# LDAQ-MINI.net
KiCad netlist of a schematic drawn in EAGLE
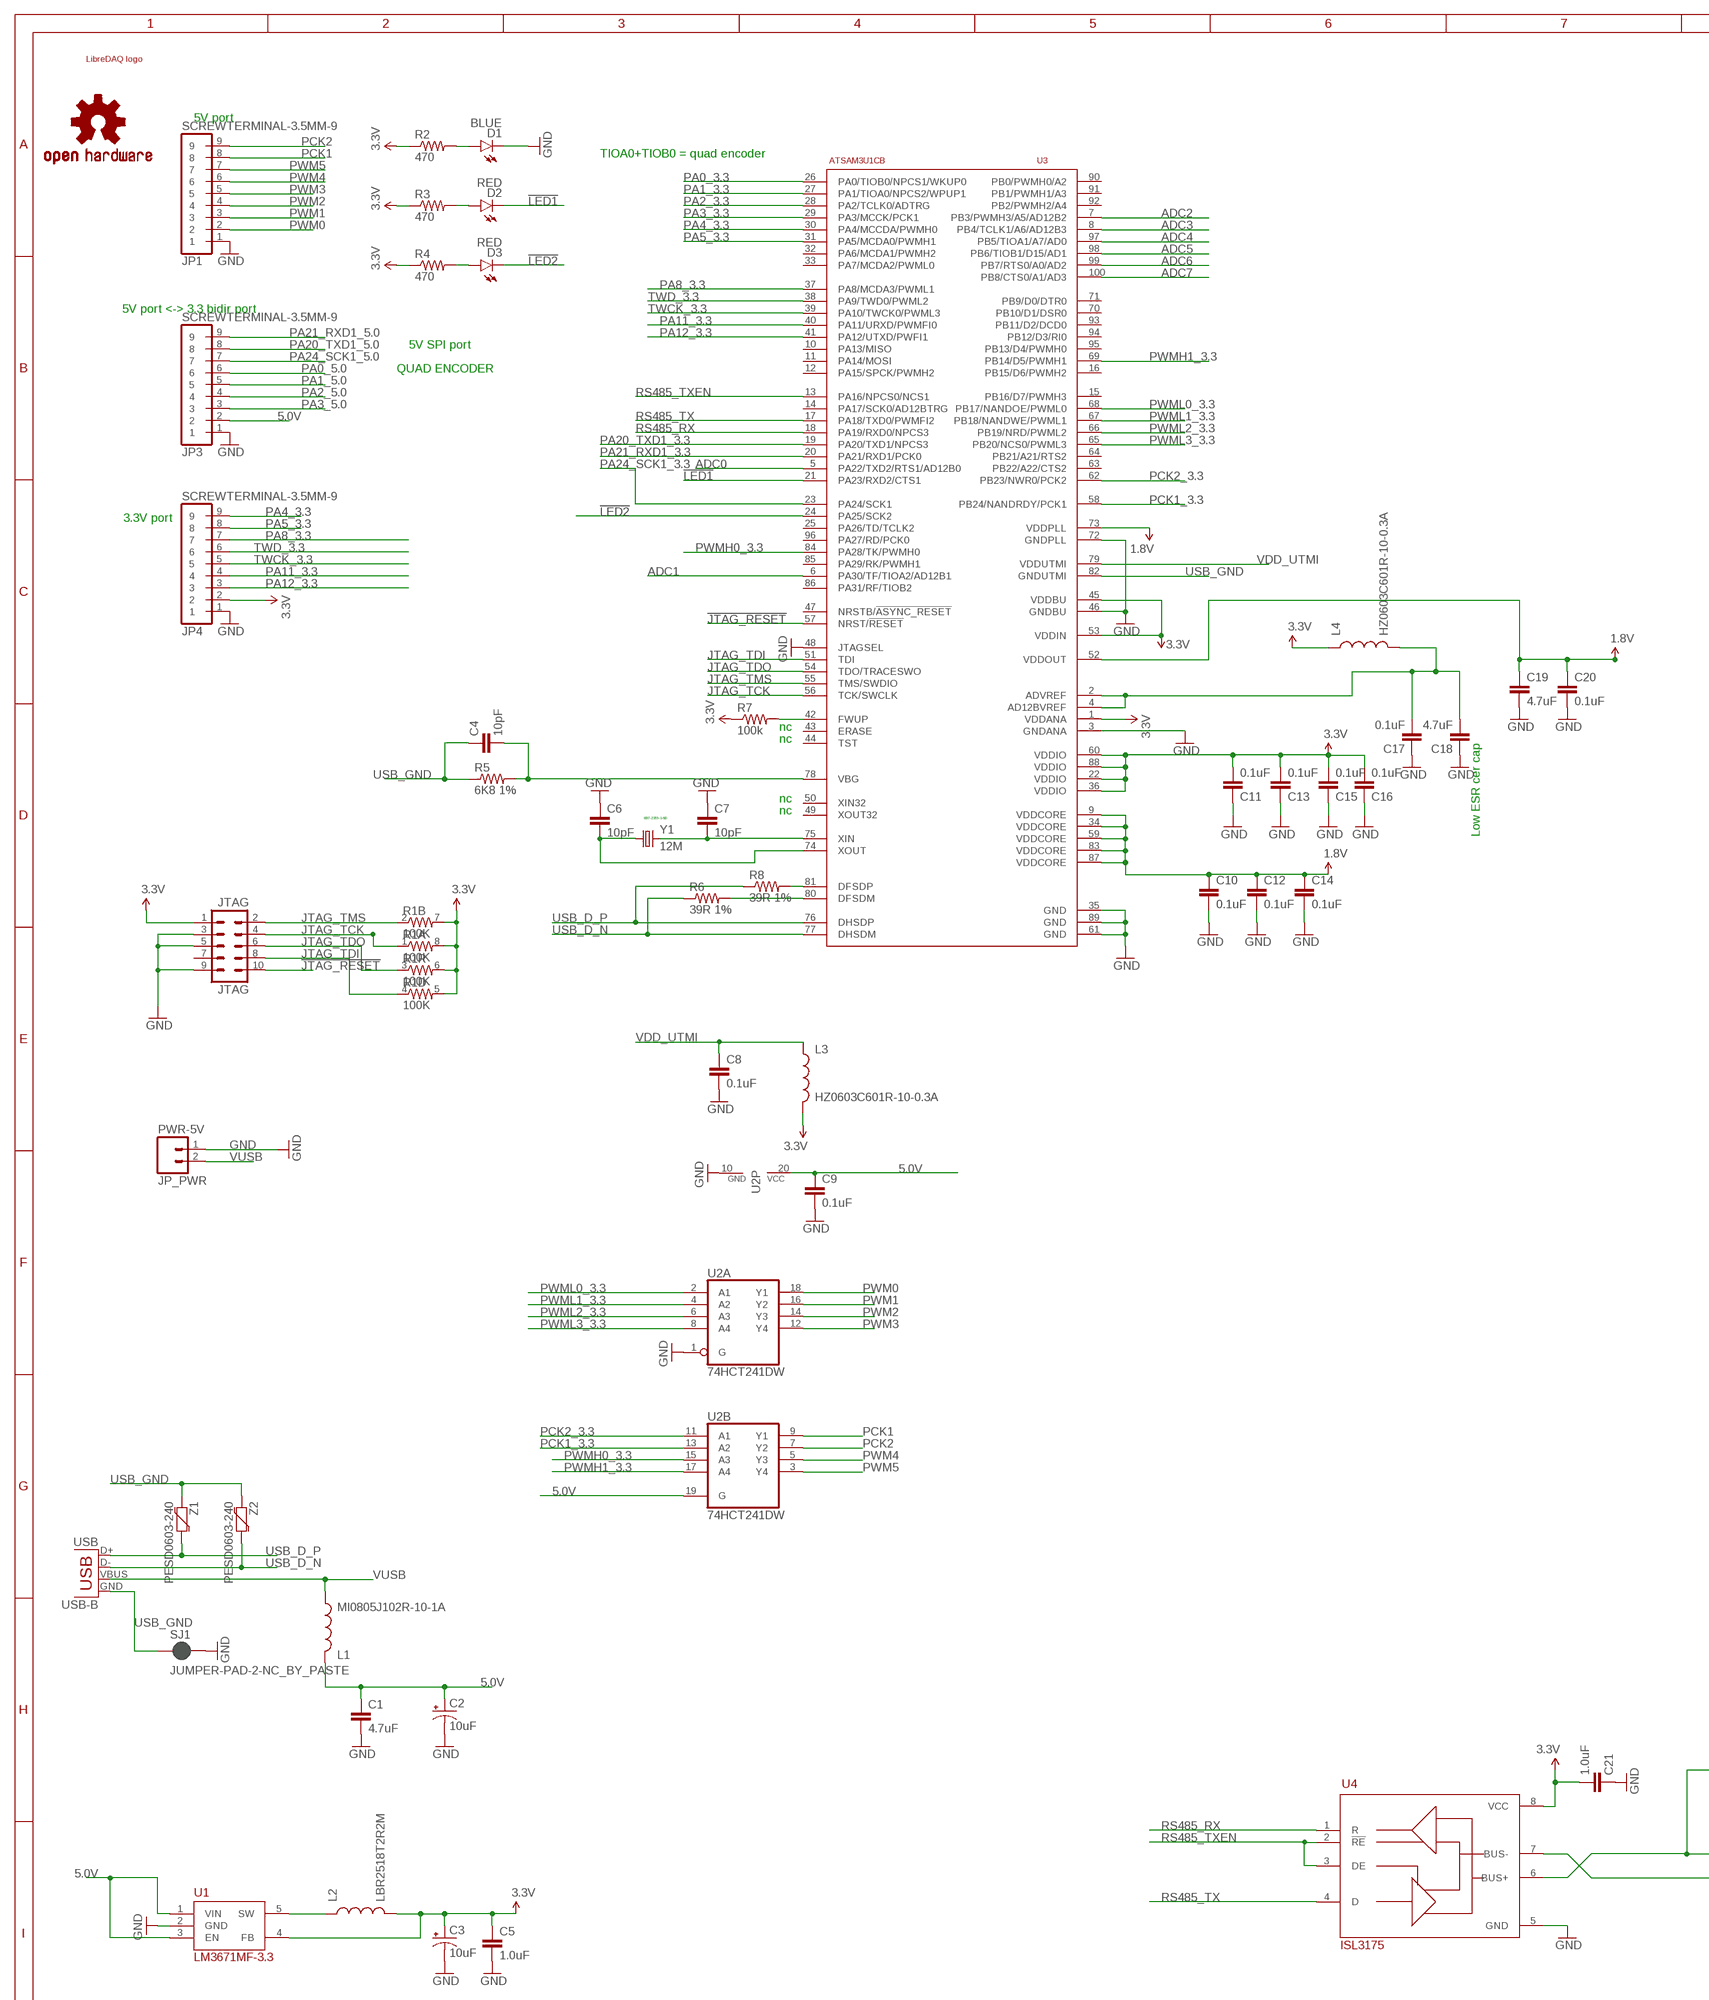
[diagram p0: schematic, sheet 1, part 1 of 2]
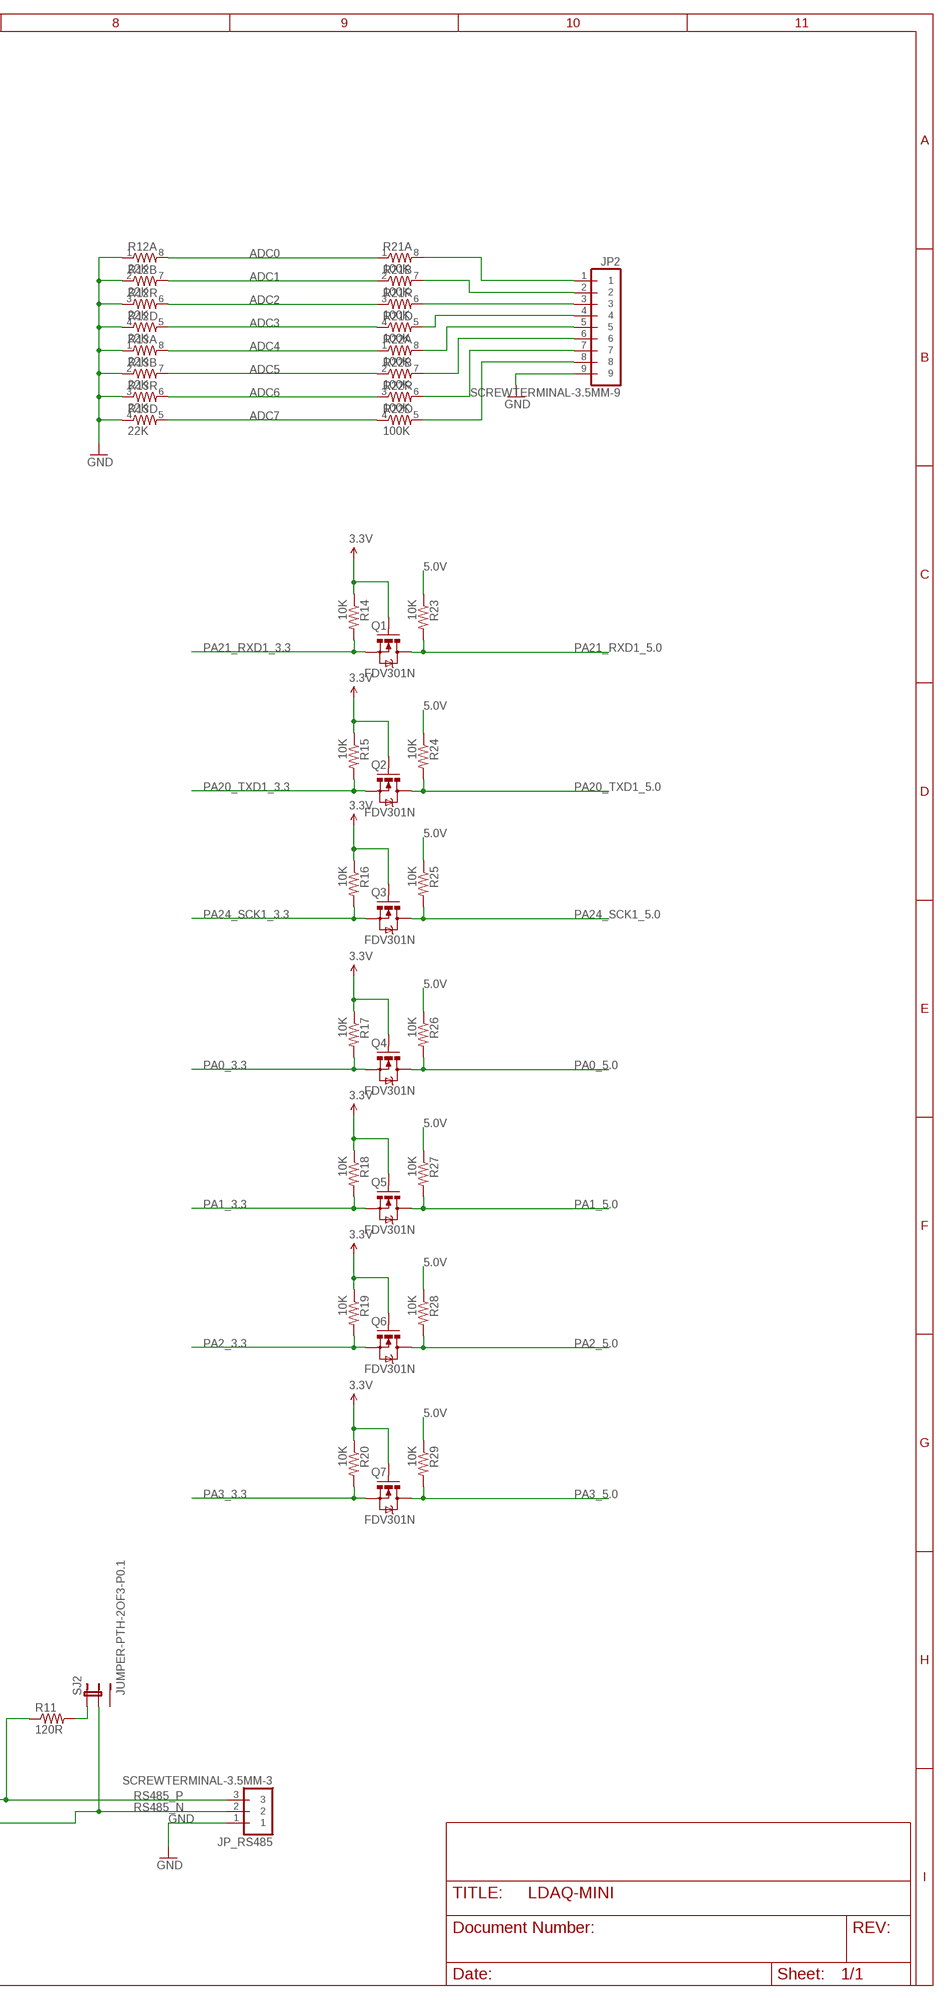
[diagram p1: schematic, sheet 1, part 2 of 2]

(export (version "E")
  (design (tool "Eeschema 10.0.6"))
  (components
    (comp (ref "C1")
      (value "4.7uF")
      (footprint "eagle-import:0603-CAP")
      (libsource (lib "eagle-import") (part "CAP0603-CAP"))
    )
    (comp (ref "C2")
      (value "10uF")
      (footprint "eagle-import:EIA3216")
      (libsource (lib "eagle-import") (part "CAP_POL1206"))
    )
    (comp (ref "C3")
      (value "10uF")
      (footprint "eagle-import:EIA3216")
      (libsource (lib "eagle-import") (part "10UF-16V-10%(TANT)"))
    )
    (comp (ref "C4")
      (value "10pF")
      (footprint "eagle-import:0603-CAP")
      (libsource (lib "eagle-import") (part "10PF-50V-5%(0603)"))
    )
    (comp (ref "C5")
      (value "1.0uF")
      (footprint "eagle-import:0805")
      (libsource (lib "eagle-import") (part "1.0UF-25V-+80/-20(0805)"))
    )
    (comp (ref "C6")
      (value "10pF")
      (footprint "eagle-import:0603-CAP")
      (libsource (lib "eagle-import") (part "22PF-50V-5%(0603)"))
    )
    (comp (ref "C7")
      (value "10pF")
      (footprint "eagle-import:0603-CAP")
      (libsource (lib "eagle-import") (part "22PF-50V-5%(0603)"))
    )
    (comp (ref "C8")
      (value "0.1uF")
      (footprint "eagle-import:0603-CAP")
      (libsource (lib "eagle-import") (part "0.1UF-25V(+80/-20%)(0603)"))
    )
    (comp (ref "C9")
      (value "0.1uF")
      (footprint "eagle-import:0603-CAP")
      (libsource (lib "eagle-import") (part "0.1UF-25V(+80/-20%)(0603)"))
    )
    (comp (ref "C10")
      (value "0.1uF")
      (footprint "eagle-import:0603-CAP")
      (libsource (lib "eagle-import") (part "0.1UF-25V(+80/-20%)(0603)"))
    )
    (comp (ref "C11")
      (value "0.1uF")
      (footprint "eagle-import:0603-CAP")
      (libsource (lib "eagle-import") (part "0.1UF-25V(+80/-20%)(0603)"))
    )
    (comp (ref "C12")
      (value "0.1uF")
      (footprint "eagle-import:0603-CAP")
      (libsource (lib "eagle-import") (part "0.1UF-25V(+80/-20%)(0603)"))
    )
    (comp (ref "C13")
      (value "0.1uF")
      (footprint "eagle-import:0603-CAP")
      (libsource (lib "eagle-import") (part "0.1UF-25V(+80/-20%)(0603)"))
    )
    (comp (ref "C14")
      (value "0.1uF")
      (footprint "eagle-import:0603-CAP")
      (libsource (lib "eagle-import") (part "0.1UF-25V(+80/-20%)(0603)"))
    )
    (comp (ref "C15")
      (value "0.1uF")
      (footprint "eagle-import:0603-CAP")
      (libsource (lib "eagle-import") (part "0.1UF-25V(+80/-20%)(0603)"))
    )
    (comp (ref "C16")
      (value "0.1uF")
      (footprint "eagle-import:0603-CAP")
      (libsource (lib "eagle-import") (part "0.1UF-25V(+80/-20%)(0603)"))
    )
    (comp (ref "C17")
      (value "0.1uF")
      (footprint "eagle-import:0603-CAP")
      (libsource (lib "eagle-import") (part "0.1UF-25V(+80/-20%)(0603)"))
    )
    (comp (ref "C18")
      (value "4.7uF")
      (footprint "eagle-import:0603-CAP")
      (libsource (lib "eagle-import") (part "10UF-6.3V-20%(0603)"))
    )
    (comp (ref "C19")
      (value "4.7uF")
      (footprint "eagle-import:0603-CAP")
      (libsource (lib "eagle-import") (part "4.7UF-6.3V-10%(0603)0603"))
    )
    (comp (ref "C20")
      (value "0.1uF")
      (footprint "eagle-import:0603-CAP")
      (libsource (lib "eagle-import") (part "0.1UF-25V(+80/-20%)(0603)"))
    )
    (comp (ref "C21")
      (value "1.0uF")
      (footprint "eagle-import:0603-CAP")
      (libsource (lib "eagle-import") (part "1.0UF-16V-10%(0603)"))
    )
    (comp (ref "D1")
      (value "BLUE")
      (footprint "eagle-import:LED-1206")
      (libsource (lib "eagle-import") (part "LED-BLUE1206"))
    )
    (comp (ref "D2")
      (value "RED")
      (footprint "eagle-import:LED-1206")
      (libsource (lib "eagle-import") (part "LED-RED1206"))
    )
    (comp (ref "D3")
      (value "RED")
      (footprint "eagle-import:LED-1206")
      (libsource (lib "eagle-import") (part "LED-RED1206"))
    )
    (comp (ref "JP1")
      (value "SCREWTERMINAL-3.5MM-9")
      (footprint "eagle-import:SCREWTERMINAL-3.5MM-9")
      (libsource (lib "eagle-import") (part "SCREWTERMINAL-3.5MM-9"))
    )
    (comp (ref "JP2")
      (value "SCREWTERMINAL-3.5MM-9")
      (footprint "eagle-import:SCREWTERMINAL-3.5MM-9")
      (libsource (lib "eagle-import") (part "SCREWTERMINAL-3.5MM-9"))
    )
    (comp (ref "JP3")
      (value "SCREWTERMINAL-3.5MM-9")
      (footprint "eagle-import:SCREWTERMINAL-3.5MM-9")
      (libsource (lib "eagle-import") (part "SCREWTERMINAL-3.5MM-9"))
    )
    (comp (ref "JP4")
      (value "SCREWTERMINAL-3.5MM-9")
      (footprint "eagle-import:SCREWTERMINAL-3.5MM-9")
      (libsource (lib "eagle-import") (part "SCREWTERMINAL-3.5MM-9"))
    )
    (comp (ref "JP_PWR")
      (value "PWR-5V")
      (footprint "eagle-import:JST-2-PTH-VERT")
      (libsource (lib "eagle-import") (part "M02JST-PTH-VERT"))
    )
    (comp (ref "JP_RS485")
      (value "SCREWTERMINAL-3.5MM-3")
      (footprint "eagle-import:SCREWTERMINAL-3.5MM-3")
      (libsource (lib "eagle-import") (part "SCREWTERMINAL-3.5MM-3"))
    )
    (comp (ref "JTAG")
      (value "JTAG")
      (footprint "eagle-import:AVR_ICSP")
      (libsource (lib "eagle-import") (part "M05X2PTH"))
    )
    (comp (ref "L1")
      (value "MI0805J102R-10-1A")
      (footprint "eagle-import:0805")
      (libsource (lib "eagle-import") (part "INDUCTOR0805"))
    )
    (comp (ref "L2")
      (value "LBR2518T2R2M")
      (footprint "eagle-import:1007")
      (libsource (lib "eagle-import") (part "INDUCTOR1007"))
    )
    (comp (ref "L3")
      (value "HZ0603C601R-10-0.3A")
      (footprint "eagle-import:0603")
      (libsource (lib "eagle-import") (part "INDUCTOR0603"))
    )
    (comp (ref "L4")
      (value "HZ0603C601R-10-0.3A")
      (footprint "eagle-import:0603")
      (libsource (lib "eagle-import") (part "INDUCTOR0603"))
    )
    (comp (ref "LOGO1")
      (value "LIBREDAQ_LOGO_MINILOGO_GENERIC")
      (footprint "eagle-import:LIBREDAQ_LOGO")
      (libsource (lib "eagle-import") (part "LIBREDAQ_LOGO_MINILOGO_GENERIC"))
    )
    (comp (ref "LOGO2")
      (value "OSHW-LOGOL")
      (footprint "eagle-import:OSHW-LOGO-L")
      (libsource (lib "eagle-import") (part "OSHW-LOGOL"))
    )
    (comp (ref "Q1")
      (value "FDV301N")
      (footprint "eagle-import:SOT23-3")
      (libsource (lib "eagle-import") (part "MOSFET-NCHANNELSMD"))
    )
    (comp (ref "Q2")
      (value "FDV301N")
      (footprint "eagle-import:SOT23-3")
      (libsource (lib "eagle-import") (part "MOSFET-NCHANNELSMD"))
    )
    (comp (ref "Q3")
      (value "FDV301N")
      (footprint "eagle-import:SOT23-3")
      (libsource (lib "eagle-import") (part "MOSFET-NCHANNELSMD"))
    )
    (comp (ref "Q4")
      (value "FDV301N")
      (footprint "eagle-import:SOT23-3")
      (libsource (lib "eagle-import") (part "MOSFET-NCHANNELSMD"))
    )
    (comp (ref "Q5")
      (value "FDV301N")
      (footprint "eagle-import:SOT23-3")
      (libsource (lib "eagle-import") (part "MOSFET-NCHANNELSMD"))
    )
    (comp (ref "Q6")
      (value "FDV301N")
      (footprint "eagle-import:SOT23-3")
      (libsource (lib "eagle-import") (part "MOSFET-NCHANNELSMD"))
    )
    (comp (ref "Q7")
      (value "FDV301N")
      (footprint "eagle-import:SOT23-3")
      (libsource (lib "eagle-import") (part "MOSFET-NCHANNELSMD"))
    )
    (comp (ref "R1")
      (value "100K")
      (footprint "eagle-import:0603-ARV")
      (libsource (lib "eagle-import") (part "RESISTOR-ARRAY0603-ARV"))
    )
    (comp (ref "R2")
      (value "470")
      (footprint "eagle-import:0603-RES")
      (libsource (lib "eagle-import") (part "470OHM1/10W1%(0603)"))
    )
    (comp (ref "R3")
      (value "470")
      (footprint "eagle-import:0603-RES")
      (libsource (lib "eagle-import") (part "470OHM1/10W1%(0603)"))
    )
    (comp (ref "R4")
      (value "470")
      (footprint "eagle-import:0603-RES")
      (libsource (lib "eagle-import") (part "470OHM1/10W1%(0603)"))
    )
    (comp (ref "R5")
      (value "6K8 1%")
      (footprint "eagle-import:0603-RES")
      (libsource (lib "eagle-import") (part "RESISTOR0603"))
    )
    (comp (ref "R6")
      (value "39R 1%")
      (footprint "eagle-import:0603-RES")
      (libsource (lib "eagle-import") (part "RESISTOR0603"))
    )
    (comp (ref "R7")
      (value "100k")
      (footprint "eagle-import:0603-RES")
      (libsource (lib "eagle-import") (part "100KOHM-1/10W-1%(0603)"))
    )
    (comp (ref "R8")
      (value "39R 1%")
      (footprint "eagle-import:1206")
      (libsource (lib "eagle-import") (part "SparkFun-Resistors_RESISTOR1206"))
    )
    (comp (ref "R11")
      (value "120R")
      (footprint "eagle-import:0603-RES")
      (libsource (lib "eagle-import") (part "RESISTOR0603"))
    )
    (comp (ref "R12")
      (value "22K")
      (footprint "eagle-import:0603-ARV")
      (libsource (lib "eagle-import") (part "RESISTOR-ARRAY0603-ARV"))
    )
    (comp (ref "R13")
      (value "22K")
      (footprint "eagle-import:0603-ARV")
      (libsource (lib "eagle-import") (part "RESISTOR-ARRAY0603-ARV"))
    )
    (comp (ref "R14")
      (value "10K")
      (footprint "eagle-import:0603-RES")
      (libsource (lib "eagle-import") (part "RESISTOR0603-RES"))
    )
    (comp (ref "R15")
      (value "10K")
      (footprint "eagle-import:0603-RES")
      (libsource (lib "eagle-import") (part "RESISTOR0603-RES"))
    )
    (comp (ref "R16")
      (value "10K")
      (footprint "eagle-import:0603-RES")
      (libsource (lib "eagle-import") (part "RESISTOR0603-RES"))
    )
    (comp (ref "R17")
      (value "10K")
      (footprint "eagle-import:0603-RES")
      (libsource (lib "eagle-import") (part "RESISTOR0603-RES"))
    )
    (comp (ref "R18")
      (value "10K")
      (footprint "eagle-import:0603-RES")
      (libsource (lib "eagle-import") (part "RESISTOR0603-RES"))
    )
    (comp (ref "R19")
      (value "10K")
      (footprint "eagle-import:0603-RES")
      (libsource (lib "eagle-import") (part "RESISTOR0603-RES"))
    )
    (comp (ref "R20")
      (value "10K")
      (footprint "eagle-import:0603-RES")
      (libsource (lib "eagle-import") (part "RESISTOR0603-RES"))
    )
    (comp (ref "R21")
      (value "100K")
      (footprint "eagle-import:0603-ARV")
      (libsource (lib "eagle-import") (part "RESISTOR-ARRAY0603-ARV"))
    )
    (comp (ref "R22")
      (value "100K")
      (footprint "eagle-import:0603-ARV")
      (libsource (lib "eagle-import") (part "RESISTOR-ARRAY0603-ARV"))
    )
    (comp (ref "R23")
      (value "10K")
      (footprint "eagle-import:0603-RES")
      (libsource (lib "eagle-import") (part "RESISTOR0603-RES"))
    )
    (comp (ref "R24")
      (value "10K")
      (footprint "eagle-import:0603-RES")
      (libsource (lib "eagle-import") (part "RESISTOR0603-RES"))
    )
    (comp (ref "R25")
      (value "10K")
      (footprint "eagle-import:0603-RES")
      (libsource (lib "eagle-import") (part "RESISTOR0603-RES"))
    )
    (comp (ref "R26")
      (value "10K")
      (footprint "eagle-import:0603-RES")
      (libsource (lib "eagle-import") (part "RESISTOR0603-RES"))
    )
    (comp (ref "R27")
      (value "10K")
      (footprint "eagle-import:0603-RES")
      (libsource (lib "eagle-import") (part "RESISTOR0603-RES"))
    )
    (comp (ref "R28")
      (value "10K")
      (footprint "eagle-import:0603-RES")
      (libsource (lib "eagle-import") (part "RESISTOR0603-RES"))
    )
    (comp (ref "R29")
      (value "10K")
      (footprint "eagle-import:0603-RES")
      (libsource (lib "eagle-import") (part "RESISTOR0603-RES"))
    )
    (comp (ref "SJ1")
      (value "JUMPER-PAD-2-NC_BY_PASTE")
      (footprint "eagle-import:PAD-JUMPER-2-NC_BY_PASTE_YES_SILK")
      (libsource (lib "eagle-import") (part "JUMPER-PAD-2-NC_BY_PASTE"))
    )
    (comp (ref "SJ2")
      (value "JUMPER-PTH-2OF3-P0.1")
      (footprint "eagle-import:1X03_LONGPADS")
      (libsource (lib "eagle-import") (part "JUMPER-PTH-2OF3-P0.1"))
    )
    (comp (ref "U1")
      (value "LM3671MF-3.3")
      (footprint "eagle-import:TOP23-5")
      (libsource (lib "eagle-import") (part "LM3671MF-3.3"))
    )
    (comp (ref "U2")
      (value "74HCT241DW")
      (footprint "eagle-import:SO20W")
      (libsource (lib "eagle-import") (part "74241DWHCT"))
    )
    (comp (ref "U3")
      (value "ATSAM3U1CB")
      (footprint "eagle-import:TQFP100")
      (libsource (lib "eagle-import") (part "ATSAM3U1CB"))
    )
    (comp (ref "U4")
      (value "ISL3175")
      (footprint "eagle-import:SOIC8")
      (libsource (lib "eagle-import") (part "ISL3175"))
    )
    (comp (ref "USB")
      (value "USB-B")
      (footprint "eagle-import:USB-B-PTH")
      (libsource (lib "eagle-import") (part "USBPTH"))
    )
    (comp (ref "Y1")
      (value "12M")
      (footprint "eagle-import:CRYSTAL-SMD-5X3")
      (libsource (lib "eagle-import") (part "CRYSTAL5X3"))
    )
    (comp (ref "Z1")
      (value "PESD0603-240")
      (footprint "eagle-import:0603-RES")
      (libsource (lib "eagle-import") (part "VARISTOR-0603"))
    )
    (comp (ref "Z2")
      (value "PESD0603-240")
      (footprint "eagle-import:0603-RES")
      (libsource (lib "eagle-import") (part "VARISTOR-0603"))
    )
  )
  (nets
    (net (code "1") (name "/5.0V") (class "Default")
      (node (ref "C1") (pin "1") (pinfunction "1_1") (pintype "passive"))
      (node (ref "C2") (pin "A") (pinfunction "+_A") (pintype "passive"))
      (node (ref "C9") (pin "1") (pinfunction "1_1") (pintype "passive"))
      (node (ref "JP3") (pin "2") (pinfunction "2_2") (pintype "bidirectional"))
      (node (ref "L1") (pin "1") (pinfunction "1_1") (pintype "passive"))
      (node (ref "R23") (pin "1") (pinfunction "1_1") (pintype "passive"))
      (node (ref "R24") (pin "1") (pinfunction "1_1") (pintype "passive"))
      (node (ref "R25") (pin "1") (pinfunction "1_1") (pintype "passive"))
      (node (ref "R26") (pin "1") (pinfunction "1_1") (pintype "passive"))
      (node (ref "R27") (pin "1") (pinfunction "1_1") (pintype "passive"))
      (node (ref "R28") (pin "1") (pinfunction "1_1") (pintype "passive"))
      (node (ref "R29") (pin "1") (pinfunction "1_1") (pintype "passive"))
      (node (ref "U1") (pin "1") (pinfunction "VIN_1") (pintype "bidirectional"))
      (node (ref "U1") (pin "3") (pinfunction "EN_3") (pintype "bidirectional"))
      (node (ref "U2") (pin "19") (pinfunction "G_19") (pintype "input"))
      (node (ref "U2") (pin "20") (pinfunction "VCC_20") (pintype "power_in"))
    )
    (net (code "2") (name "/ADC0") (class "Default")
      (node (ref "R12") (pin "8") (pinfunction "2_8") (pintype "passive"))
      (node (ref "R21") (pin "1") (pinfunction "1_1") (pintype "passive"))
      (node (ref "U3") (pin "5") (pinfunction "PA22/TXD2/RTS1/AD12B0_5") (pintype "bidirectional"))
    )
    (net (code "3") (name "/ADC1") (class "Default")
      (node (ref "R12") (pin "7") (pinfunction "2_7") (pintype "passive"))
      (node (ref "R21") (pin "2") (pinfunction "1_2") (pintype "passive"))
      (node (ref "U3") (pin "6") (pinfunction "PA30/TF/TIOA2/AD12B1_6") (pintype "bidirectional"))
    )
    (net (code "4") (name "/ADC2") (class "Default")
      (node (ref "R12") (pin "6") (pinfunction "2_6") (pintype "passive"))
      (node (ref "R21") (pin "3") (pinfunction "1_3") (pintype "passive"))
      (node (ref "U3") (pin "7") (pinfunction "PB3/PWMH3/A5/AD12B2_7") (pintype "bidirectional"))
    )
    (net (code "5") (name "/ADC3") (class "Default")
      (node (ref "R12") (pin "5") (pinfunction "2_5") (pintype "passive"))
      (node (ref "R21") (pin "4") (pinfunction "1_4") (pintype "passive"))
      (node (ref "U3") (pin "8") (pinfunction "PB4/TCLK1/A6/AD12B3_8") (pintype "bidirectional"))
    )
    (net (code "6") (name "/ADC4") (class "Default")
      (node (ref "R13") (pin "8") (pinfunction "2_8") (pintype "passive"))
      (node (ref "R22") (pin "1") (pinfunction "1_1") (pintype "passive"))
      (node (ref "U3") (pin "97") (pinfunction "PB5/TIOA1/A7/AD0_97") (pintype "bidirectional"))
    )
    (net (code "7") (name "/ADC5") (class "Default")
      (node (ref "R13") (pin "7") (pinfunction "2_7") (pintype "passive"))
      (node (ref "R22") (pin "2") (pinfunction "1_2") (pintype "passive"))
      (node (ref "U3") (pin "98") (pinfunction "PB6/TIOB1/D15/AD1_98") (pintype "bidirectional"))
    )
    (net (code "8") (name "/ADC6") (class "Default")
      (node (ref "R13") (pin "6") (pinfunction "2_6") (pintype "passive"))
      (node (ref "R22") (pin "3") (pinfunction "1_3") (pintype "passive"))
      (node (ref "U3") (pin "99") (pinfunction "PB7/RTS0/A0/AD2_99") (pintype "bidirectional"))
    )
    (net (code "9") (name "/ADC7") (class "Default")
      (node (ref "R13") (pin "5") (pinfunction "2_5") (pintype "passive"))
      (node (ref "R22") (pin "4") (pinfunction "1_4") (pintype "passive"))
      (node (ref "U3") (pin "100") (pinfunction "PB8/CTS0/A1/AD3_100") (pintype "bidirectional"))
    )
    (net (code "10") (name "/JTAG_TCK") (class "Default")
      (node (ref "JTAG") (pin "4") (pinfunction "4_4") (pintype "passive"))
      (node (ref "R1") (pin "1") (pinfunction "1_1") (pintype "passive"))
      (node (ref "U3") (pin "56") (pinfunction "TCK/SWCLK_56") (pintype "bidirectional"))
    )
    (net (code "11") (name "/JTAG_TDI") (class "Default")
      (node (ref "JTAG") (pin "8") (pinfunction "8_8") (pintype "passive"))
      (node (ref "R1") (pin "4") (pinfunction "1_4") (pintype "passive"))
      (node (ref "U3") (pin "51") (pinfunction "TDI_51") (pintype "bidirectional"))
    )
    (net (code "12") (name "/JTAG_TDO") (class "Default")
      (node (ref "JTAG") (pin "6") (pinfunction "6_6") (pintype "passive"))
      (node (ref "R1") (pin "3") (pinfunction "1_3") (pintype "passive"))
      (node (ref "U3") (pin "54") (pinfunction "TDO/TRACESWO_54") (pintype "bidirectional"))
    )
    (net (code "13") (name "/JTAG_TMS") (class "Default")
      (node (ref "JTAG") (pin "2") (pinfunction "2_2") (pintype "passive"))
      (node (ref "R1") (pin "2") (pinfunction "1_2") (pintype "passive"))
      (node (ref "U3") (pin "55") (pinfunction "TMS/SWDIO_55") (pintype "bidirectional"))
    )
    (net (code "14") (name "/PA0_3.3") (class "Default")
      (node (ref "Q4") (pin "2") (pinfunction "S_2") (pintype "passive"))
      (node (ref "R17") (pin "2") (pinfunction "2_2") (pintype "passive"))
      (node (ref "U3") (pin "26") (pinfunction "PA0/TIOB0/NPCS1/WKUP0_26") (pintype "bidirectional"))
    )
    (net (code "15") (name "/PA0_5.0") (class "Default")
      (node (ref "JP3") (pin "6") (pinfunction "6_6") (pintype "bidirectional"))
      (node (ref "Q4") (pin "3") (pinfunction "D_3") (pintype "passive"))
      (node (ref "R26") (pin "2") (pinfunction "2_2") (pintype "passive"))
    )
    (net (code "16") (name "/PA1_3.3") (class "Default")
      (node (ref "Q5") (pin "2") (pinfunction "S_2") (pintype "passive"))
      (node (ref "R18") (pin "2") (pinfunction "2_2") (pintype "passive"))
      (node (ref "U3") (pin "27") (pinfunction "PA1/TIOA0/NPCS2/WPUP1_27") (pintype "bidirectional"))
    )
    (net (code "17") (name "/PA1_5.0") (class "Default")
      (node (ref "JP3") (pin "5") (pinfunction "5_5") (pintype "bidirectional"))
      (node (ref "Q5") (pin "3") (pinfunction "D_3") (pintype "passive"))
      (node (ref "R27") (pin "2") (pinfunction "2_2") (pintype "passive"))
    )
    (net (code "18") (name "/PA2_3.3") (class "Default")
      (node (ref "Q6") (pin "2") (pinfunction "S_2") (pintype "passive"))
      (node (ref "R19") (pin "2") (pinfunction "2_2") (pintype "passive"))
      (node (ref "U3") (pin "28") (pinfunction "PA2/TCLK0/ADTRG_28") (pintype "bidirectional"))
    )
    (net (code "19") (name "/PA2_5.0") (class "Default")
      (node (ref "JP3") (pin "4") (pinfunction "4_4") (pintype "bidirectional"))
      (node (ref "Q6") (pin "3") (pinfunction "D_3") (pintype "passive"))
      (node (ref "R28") (pin "2") (pinfunction "2_2") (pintype "passive"))
    )
    (net (code "20") (name "/PA3_3.3") (class "Default")
      (node (ref "Q7") (pin "2") (pinfunction "S_2") (pintype "passive"))
      (node (ref "R20") (pin "2") (pinfunction "2_2") (pintype "passive"))
      (node (ref "U3") (pin "29") (pinfunction "PA3/MCCK/PCK1_29") (pintype "bidirectional"))
    )
    (net (code "21") (name "/PA3_5.0") (class "Default")
      (node (ref "JP3") (pin "3") (pinfunction "3_3") (pintype "bidirectional"))
      (node (ref "Q7") (pin "3") (pinfunction "D_3") (pintype "passive"))
      (node (ref "R29") (pin "2") (pinfunction "2_2") (pintype "passive"))
    )
    (net (code "22") (name "/PA4_3.3") (class "Default")
      (node (ref "JP4") (pin "9") (pinfunction "9_9") (pintype "bidirectional"))
      (node (ref "U3") (pin "30") (pinfunction "PA4/MCCDA/PWMH0_30") (pintype "bidirectional"))
    )
    (net (code "23") (name "/PA5_3.3") (class "Default")
      (node (ref "JP4") (pin "8") (pinfunction "8_8") (pintype "bidirectional"))
      (node (ref "U3") (pin "31") (pinfunction "PA5/MCDA0/PWMH1_31") (pintype "bidirectional"))
    )
    (net (code "24") (name "/PA8_3.3") (class "Default")
      (node (ref "JP4") (pin "7") (pinfunction "7_7") (pintype "bidirectional"))
      (node (ref "U3") (pin "37") (pinfunction "PA8/MCDA3/PWML1_37") (pintype "bidirectional"))
    )
    (net (code "25") (name "/PA11_3.3") (class "Default")
      (node (ref "JP4") (pin "4") (pinfunction "4_4") (pintype "bidirectional"))
      (node (ref "U3") (pin "40") (pinfunction "PA11/URXD/PWMFI0_40") (pintype "bidirectional"))
    )
    (net (code "26") (name "/PA12_3.3") (class "Default")
      (node (ref "JP4") (pin "3") (pinfunction "3_3") (pintype "bidirectional"))
      (node (ref "U3") (pin "41") (pinfunction "PA12/UTXD/PWFI1_41") (pintype "bidirectional"))
    )
    (net (code "27") (name "/PA20_TXD1_3.3") (class "Default")
      (node (ref "Q2") (pin "2") (pinfunction "S_2") (pintype "passive"))
      (node (ref "R15") (pin "2") (pinfunction "2_2") (pintype "passive"))
      (node (ref "U3") (pin "19") (pinfunction "PA20/TXD1/NPCS3_19") (pintype "bidirectional"))
    )
    (net (code "28") (name "/PA20_TXD1_5.0") (class "Default")
      (node (ref "JP3") (pin "8") (pinfunction "8_8") (pintype "bidirectional"))
      (node (ref "Q2") (pin "3") (pinfunction "D_3") (pintype "passive"))
      (node (ref "R24") (pin "2") (pinfunction "2_2") (pintype "passive"))
    )
    (net (code "29") (name "/PA21_RXD1_3.3") (class "Default")
      (node (ref "Q1") (pin "2") (pinfunction "S_2") (pintype "passive"))
      (node (ref "R14") (pin "2") (pinfunction "2_2") (pintype "passive"))
      (node (ref "U3") (pin "20") (pinfunction "PA21/RXD1/PCK0_20") (pintype "bidirectional"))
    )
    (net (code "30") (name "/PA21_RXD1_5.0") (class "Default")
      (node (ref "JP3") (pin "9") (pinfunction "9_9") (pintype "bidirectional"))
      (node (ref "Q1") (pin "3") (pinfunction "D_3") (pintype "passive"))
      (node (ref "R23") (pin "2") (pinfunction "2_2") (pintype "passive"))
    )
    (net (code "31") (name "/PA24_SCK1_3.3") (class "Default")
      (node (ref "Q3") (pin "2") (pinfunction "S_2") (pintype "passive"))
      (node (ref "R16") (pin "2") (pinfunction "2_2") (pintype "passive"))
      (node (ref "U3") (pin "23") (pinfunction "PA24/SCK1_23") (pintype "bidirectional"))
    )
    (net (code "32") (name "/PA24_SCK1_5.0") (class "Default")
      (node (ref "JP3") (pin "7") (pinfunction "7_7") (pintype "bidirectional"))
      (node (ref "Q3") (pin "3") (pinfunction "D_3") (pintype "passive"))
      (node (ref "R25") (pin "2") (pinfunction "2_2") (pintype "passive"))
    )
    (net (code "33") (name "/PCK1") (class "Default")
      (node (ref "JP1") (pin "8") (pinfunction "8_8") (pintype "bidirectional"))
      (node (ref "U2") (pin "9") (pinfunction "Y1_9") (pintype "tri_state"))
    )
    (net (code "34") (name "/PCK1_3.3") (class "Default")
      (node (ref "U2") (pin "13") (pinfunction "A2_13") (pintype "input"))
      (node (ref "U3") (pin "58") (pinfunction "PB24/NANDRDY/PCK1_58") (pintype "bidirectional"))
    )
    (net (code "35") (name "/PCK2") (class "Default")
      (node (ref "JP1") (pin "9") (pinfunction "9_9") (pintype "bidirectional"))
      (node (ref "U2") (pin "7") (pinfunction "Y2_7") (pintype "tri_state"))
    )
    (net (code "36") (name "/PCK2_3.3") (class "Default")
      (node (ref "U2") (pin "11") (pinfunction "A1_11") (pintype "input"))
      (node (ref "U3") (pin "62") (pinfunction "PB23/NWR0/PCK2_62") (pintype "bidirectional"))
    )
    (net (code "37") (name "/PWM0") (class "Default")
      (node (ref "JP1") (pin "2") (pinfunction "2_2") (pintype "bidirectional"))
      (node (ref "U2") (pin "18") (pinfunction "Y1_18") (pintype "tri_state"))
    )
    (net (code "38") (name "/PWM1") (class "Default")
      (node (ref "JP1") (pin "3") (pinfunction "3_3") (pintype "bidirectional"))
      (node (ref "U2") (pin "16") (pinfunction "Y2_16") (pintype "tri_state"))
    )
    (net (code "39") (name "/PWM2") (class "Default")
      (node (ref "JP1") (pin "4") (pinfunction "4_4") (pintype "bidirectional"))
      (node (ref "U2") (pin "14") (pinfunction "Y3_14") (pintype "tri_state"))
    )
    (net (code "40") (name "/PWM3") (class "Default")
      (node (ref "JP1") (pin "5") (pinfunction "5_5") (pintype "bidirectional"))
      (node (ref "U2") (pin "12") (pinfunction "Y4_12") (pintype "tri_state"))
    )
    (net (code "41") (name "/PWM4") (class "Default")
      (node (ref "JP1") (pin "6") (pinfunction "6_6") (pintype "bidirectional"))
      (node (ref "U2") (pin "5") (pinfunction "Y3_5") (pintype "tri_state"))
    )
    (net (code "42") (name "/PWM5") (class "Default")
      (node (ref "JP1") (pin "7") (pinfunction "7_7") (pintype "bidirectional"))
      (node (ref "U2") (pin "3") (pinfunction "Y4_3") (pintype "tri_state"))
    )
    (net (code "43") (name "/PWMH0_3.3") (class "Default")
      (node (ref "U2") (pin "15") (pinfunction "A3_15") (pintype "input"))
      (node (ref "U3") (pin "84") (pinfunction "PA28/TK/PWMH0_84") (pintype "bidirectional"))
    )
    (net (code "44") (name "/PWMH1_3.3") (class "Default")
      (node (ref "U2") (pin "17") (pinfunction "A4_17") (pintype "input"))
      (node (ref "U3") (pin "69") (pinfunction "PB14/D5/PWMH1_69") (pintype "bidirectional"))
    )
    (net (code "45") (name "/PWML0_3.3") (class "Default")
      (node (ref "U2") (pin "2") (pinfunction "A1_2") (pintype "input"))
      (node (ref "U3") (pin "68") (pinfunction "PB17/NANDOE/PWML0_68") (pintype "bidirectional"))
    )
    (net (code "46") (name "/PWML1_3.3") (class "Default")
      (node (ref "U2") (pin "4") (pinfunction "A2_4") (pintype "input"))
      (node (ref "U3") (pin "67") (pinfunction "PB18/NANDWE/PWML1_67") (pintype "bidirectional"))
    )
    (net (code "47") (name "/PWML2_3.3") (class "Default")
      (node (ref "U2") (pin "6") (pinfunction "A3_6") (pintype "input"))
      (node (ref "U3") (pin "66") (pinfunction "PB19/NRD/PWML2_66") (pintype "bidirectional"))
    )
    (net (code "48") (name "/PWML3_3.3") (class "Default")
      (node (ref "U2") (pin "8") (pinfunction "A4_8") (pintype "input"))
      (node (ref "U3") (pin "65") (pinfunction "PB20/NCS0/PWML3_65") (pintype "bidirectional"))
    )
    (net (code "49") (name "/RS485_N") (class "Default")
      (node (ref "JP_RS485") (pin "2") (pinfunction "2_2") (pintype "bidirectional"))
      (node (ref "SJ2") (pin "2") (pinfunction "2_2") (pintype "passive"))
      (node (ref "U4") (pin "7") (pinfunction "BUS-_7") (pintype "bidirectional"))
    )
    (net (code "50") (name "/RS485_P") (class "Default")
      (node (ref "JP_RS485") (pin "3") (pinfunction "3_3") (pintype "bidirectional"))
      (node (ref "R11") (pin "1") (pinfunction "1_1") (pintype "passive"))
      (node (ref "U4") (pin "6") (pinfunction "BUS+_6") (pintype "bidirectional"))
    )
    (net (code "51") (name "/RS485_RX") (class "Default")
      (node (ref "U3") (pin "18") (pinfunction "PA19/RXD0/NPCS3_18") (pintype "bidirectional"))
      (node (ref "U4") (pin "1") (pinfunction "R_1") (pintype "bidirectional"))
    )
    (net (code "52") (name "/RS485_TX") (class "Default")
      (node (ref "U3") (pin "17") (pinfunction "PA18/TXD0/PWMFI2_17") (pintype "bidirectional"))
      (node (ref "U4") (pin "4") (pinfunction "D_4") (pintype "bidirectional"))
    )
    (net (code "53") (name "/RS485_TXEN") (class "Default")
      (node (ref "U3") (pin "13") (pinfunction "PA16/NPCS0/NCS1_13") (pintype "bidirectional"))
      (node (ref "U4") (pin "2") (pinfunction "~{RE}_2") (pintype "bidirectional"))
      (node (ref "U4") (pin "3") (pinfunction "DE_3") (pintype "bidirectional"))
    )
    (net (code "54") (name "/TWCK_3.3") (class "Default")
      (node (ref "JP4") (pin "5") (pinfunction "5_5") (pintype "bidirectional"))
      (node (ref "U3") (pin "39") (pinfunction "PA10/TWCK0/PWML3_39") (pintype "bidirectional"))
    )
    (net (code "55") (name "/TWD_3.3") (class "Default")
      (node (ref "JP4") (pin "6") (pinfunction "6_6") (pintype "bidirectional"))
      (node (ref "U3") (pin "38") (pinfunction "PA9/TWD0/PWML2_38") (pintype "bidirectional"))
    )
    (net (code "56") (name "/USB_D_N") (class "Default")
      (node (ref "R6") (pin "1") (pinfunction "1_1") (pintype "passive"))
      (node (ref "U3") (pin "77") (pinfunction "DHSDM_77") (pintype "bidirectional"))
      (node (ref "USB") (pin "D-") (pinfunction "D-_D-") (pintype "bidirectional"))
      (node (ref "Z2") (pin "2") (pinfunction "2_2") (pintype "passive"))
    )
    (net (code "57") (name "/USB_D_P") (class "Default")
      (node (ref "R8") (pin "1") (pinfunction "1_1") (pintype "passive"))
      (node (ref "U3") (pin "76") (pinfunction "DHSDP_76") (pintype "bidirectional"))
      (node (ref "USB") (pin "D+") (pinfunction "D+_D+") (pintype "bidirectional"))
      (node (ref "Z1") (pin "2") (pinfunction "2_2") (pintype "passive"))
    )
    (net (code "58") (name "/USB_GND") (class "Default")
      (node (ref "C4") (pin "1") (pinfunction "1_1") (pintype "passive"))
      (node (ref "R5") (pin "1") (pinfunction "1_1") (pintype "passive"))
      (node (ref "SJ1") (pin "1") (pinfunction "1_1") (pintype "passive"))
      (node (ref "U3") (pin "82") (pinfunction "GNDUTMI_82") (pintype "bidirectional"))
      (node (ref "USB") (pin "GND") (pinfunction "GND_GND") (pintype "bidirectional"))
      (node (ref "Z1") (pin "1") (pinfunction "1_1") (pintype "passive"))
      (node (ref "Z2") (pin "1") (pinfunction "1_1") (pintype "passive"))
    )
    (net (code "59") (name "/VDD_UTMI") (class "Default")
      (node (ref "C8") (pin "1") (pinfunction "1_1") (pintype "passive"))
      (node (ref "L3") (pin "1") (pinfunction "1_1") (pintype "passive"))
      (node (ref "U3") (pin "79") (pinfunction "VDDUTMI_79") (pintype "bidirectional"))
    )
    (net (code "60") (name "/VUSB") (class "Default")
      (node (ref "JP_PWR") (pin "2") (pinfunction "2_2") (pintype "passive"))
      (node (ref "L1") (pin "2") (pinfunction "2_2") (pintype "passive"))
      (node (ref "USB") (pin "VBUS") (pinfunction "VBUS_VBUS") (pintype "bidirectional"))
    )
    (net (code "61") (name "/~{JTAG_RESET}") (class "Default")
      (node (ref "JTAG") (pin "10") (pinfunction "10_10") (pintype "passive"))
      (node (ref "U3") (pin "57") (pinfunction "NRST/~{RESET}_57") (pintype "bidirectional"))
    )
    (net (code "62") (name "/~{LED1}") (class "Default")
      (node (ref "D2") (pin "C") (pinfunction "C_C") (pintype "passive"))
      (node (ref "U3") (pin "21") (pinfunction "PA23/RXD2/CTS1_21") (pintype "bidirectional"))
    )
    (net (code "63") (name "/~{LED2}") (class "Default")
      (node (ref "D3") (pin "C") (pinfunction "C_C") (pintype "passive"))
      (node (ref "U3") (pin "24") (pinfunction "PA25/SCK2_24") (pintype "bidirectional"))
    )
    (net (code "64") (name "1.8V") (class "Default")
      (node (ref "C10") (pin "1") (pinfunction "1_1") (pintype "passive"))
      (node (ref "C12") (pin "1") (pinfunction "1_1") (pintype "passive"))
      (node (ref "C14") (pin "1") (pinfunction "1_1") (pintype "passive"))
      (node (ref "C19") (pin "1") (pinfunction "1_1") (pintype "passive"))
      (node (ref "C20") (pin "1") (pinfunction "1_1") (pintype "passive"))
      (node (ref "U3") (pin "34") (pinfunction "VDDCORE_34") (pintype "bidirectional"))
      (node (ref "U3") (pin "52") (pinfunction "VDDOUT_52") (pintype "bidirectional"))
      (node (ref "U3") (pin "59") (pinfunction "VDDCORE_59") (pintype "bidirectional"))
      (node (ref "U3") (pin "73") (pinfunction "VDDPLL_73") (pintype "bidirectional"))
      (node (ref "U3") (pin "83") (pinfunction "VDDCORE_83") (pintype "bidirectional"))
      (node (ref "U3") (pin "87") (pinfunction "VDDCORE_87") (pintype "bidirectional"))
      (node (ref "U3") (pin "9") (pinfunction "VDDCORE_9") (pintype "bidirectional"))
    )
    (net (code "65") (name "3.3V") (class "Default")
      (node (ref "C11") (pin "2") (pinfunction "2_2") (pintype "passive"))
      (node (ref "C13") (pin "2") (pinfunction "2_2") (pintype "passive"))
      (node (ref "C15") (pin "2") (pinfunction "2_2") (pintype "passive"))
      (node (ref "C16") (pin "2") (pinfunction "2_2") (pintype "passive"))
      (node (ref "C21") (pin "2") (pinfunction "2_2") (pintype "passive"))
      (node (ref "C3") (pin "A") (pinfunction "+_A") (pintype "passive"))
      (node (ref "C5") (pin "1") (pinfunction "1_1") (pintype "passive"))
      (node (ref "JP4") (pin "2") (pinfunction "2_2") (pintype "bidirectional"))
      (node (ref "JTAG") (pin "1") (pinfunction "1_1") (pintype "passive"))
      (node (ref "L2") (pin "2") (pinfunction "2_2") (pintype "passive"))
      (node (ref "L3") (pin "2") (pinfunction "2_2") (pintype "passive"))
      (node (ref "L4") (pin "1") (pinfunction "1_1") (pintype "passive"))
      (node (ref "Q1") (pin "1") (pinfunction "G_1") (pintype "passive"))
      (node (ref "Q2") (pin "1") (pinfunction "G_1") (pintype "passive"))
      (node (ref "Q3") (pin "1") (pinfunction "G_1") (pintype "passive"))
      (node (ref "Q4") (pin "1") (pinfunction "G_1") (pintype "passive"))
      (node (ref "Q5") (pin "1") (pinfunction "G_1") (pintype "passive"))
      (node (ref "Q6") (pin "1") (pinfunction "G_1") (pintype "passive"))
      (node (ref "Q7") (pin "1") (pinfunction "G_1") (pintype "passive"))
      (node (ref "R1") (pin "5") (pinfunction "2_5") (pintype "passive"))
      (node (ref "R1") (pin "6") (pinfunction "2_6") (pintype "passive"))
      (node (ref "R1") (pin "7") (pinfunction "2_7") (pintype "passive"))
      (node (ref "R1") (pin "8") (pinfunction "2_8") (pintype "passive"))
      (node (ref "R14") (pin "1") (pinfunction "1_1") (pintype "passive"))
      (node (ref "R15") (pin "1") (pinfunction "1_1") (pintype "passive"))
      (node (ref "R16") (pin "1") (pinfunction "1_1") (pintype "passive"))
      (node (ref "R17") (pin "1") (pinfunction "1_1") (pintype "passive"))
      (node (ref "R18") (pin "1") (pinfunction "1_1") (pintype "passive"))
      (node (ref "R19") (pin "1") (pinfunction "1_1") (pintype "passive"))
      (node (ref "R2") (pin "1") (pinfunction "1_1") (pintype "passive"))
      (node (ref "R20") (pin "1") (pinfunction "1_1") (pintype "passive"))
      (node (ref "R3") (pin "1") (pinfunction "1_1") (pintype "passive"))
      (node (ref "R4") (pin "1") (pinfunction "1_1") (pintype "passive"))
      (node (ref "R7") (pin "1") (pinfunction "1_1") (pintype "passive"))
      (node (ref "U1") (pin "4") (pinfunction "FB_4") (pintype "bidirectional"))
      (node (ref "U3") (pin "1") (pinfunction "VDDANA_1") (pintype "bidirectional"))
      (node (ref "U3") (pin "22") (pinfunction "VDDIO_22") (pintype "bidirectional"))
      (node (ref "U3") (pin "36") (pinfunction "VDDIO_36") (pintype "bidirectional"))
      (node (ref "U3") (pin "45") (pinfunction "VDDBU_45") (pintype "bidirectional"))
      (node (ref "U3") (pin "53") (pinfunction "VDDIN_53") (pintype "bidirectional"))
      (node (ref "U3") (pin "60") (pinfunction "VDDIO_60") (pintype "bidirectional"))
      (node (ref "U3") (pin "88") (pinfunction "VDDIO_88") (pintype "bidirectional"))
      (node (ref "U4") (pin "8") (pinfunction "VCC_8") (pintype "bidirectional"))
    )
    (net (code "66") (name "GND") (class "Default")
      (node (ref "C1") (pin "2") (pinfunction "2_2") (pintype "passive"))
      (node (ref "C10") (pin "2") (pinfunction "2_2") (pintype "passive"))
      (node (ref "C11") (pin "1") (pinfunction "1_1") (pintype "passive"))
      (node (ref "C12") (pin "2") (pinfunction "2_2") (pintype "passive"))
      (node (ref "C13") (pin "1") (pinfunction "1_1") (pintype "passive"))
      (node (ref "C14") (pin "2") (pinfunction "2_2") (pintype "passive"))
      (node (ref "C15") (pin "1") (pinfunction "1_1") (pintype "passive"))
      (node (ref "C16") (pin "1") (pinfunction "1_1") (pintype "passive"))
      (node (ref "C17") (pin "1") (pinfunction "1_1") (pintype "passive"))
      (node (ref "C18") (pin "1") (pinfunction "1_1") (pintype "passive"))
      (node (ref "C19") (pin "2") (pinfunction "2_2") (pintype "passive"))
      (node (ref "C2") (pin "C") (pinfunction "-_C") (pintype "passive"))
      (node (ref "C20") (pin "2") (pinfunction "2_2") (pintype "passive"))
      (node (ref "C21") (pin "1") (pinfunction "1_1") (pintype "passive"))
      (node (ref "C3") (pin "C") (pinfunction "-_C") (pintype "passive"))
      (node (ref "C5") (pin "2") (pinfunction "2_2") (pintype "passive"))
      (node (ref "C6") (pin "1") (pinfunction "1_1") (pintype "passive"))
      (node (ref "C7") (pin "1") (pinfunction "1_1") (pintype "passive"))
      (node (ref "C8") (pin "2") (pinfunction "2_2") (pintype "passive"))
      (node (ref "C9") (pin "2") (pinfunction "2_2") (pintype "passive"))
      (node (ref "D1") (pin "C") (pinfunction "C_C") (pintype "passive"))
      (node (ref "JP1") (pin "1") (pinfunction "1_1") (pintype "bidirectional"))
      (node (ref "JP2") (pin "9") (pinfunction "9_9") (pintype "bidirectional"))
      (node (ref "JP3") (pin "1") (pinfunction "1_1") (pintype "bidirectional"))
      (node (ref "JP4") (pin "1") (pinfunction "1_1") (pintype "bidirectional"))
      (node (ref "JP_PWR") (pin "1") (pinfunction "1_1") (pintype "passive"))
      (node (ref "JP_RS485") (pin "1") (pinfunction "1_1") (pintype "bidirectional"))
      (node (ref "JTAG") (pin "3") (pinfunction "3_3") (pintype "passive"))
      (node (ref "JTAG") (pin "5") (pinfunction "5_5") (pintype "passive"))
      (node (ref "JTAG") (pin "9") (pinfunction "9_9") (pintype "passive"))
      (node (ref "R12") (pin "1") (pinfunction "1_1") (pintype "passive"))
      (node (ref "R12") (pin "2") (pinfunction "1_2") (pintype "passive"))
      (node (ref "R12") (pin "3") (pinfunction "1_3") (pintype "passive"))
      (node (ref "R12") (pin "4") (pinfunction "1_4") (pintype "passive"))
      (node (ref "R13") (pin "1") (pinfunction "1_1") (pintype "passive"))
      (node (ref "R13") (pin "2") (pinfunction "1_2") (pintype "passive"))
      (node (ref "R13") (pin "3") (pinfunction "1_3") (pintype "passive"))
      (node (ref "R13") (pin "4") (pinfunction "1_4") (pintype "passive"))
      (node (ref "SJ1") (pin "2") (pinfunction "2_2") (pintype "passive"))
      (node (ref "U1") (pin "2") (pinfunction "GND_2") (pintype "bidirectional"))
      (node (ref "U2") (pin "1") (pinfunction "G_1") (pintype "input"))
      (node (ref "U2") (pin "10") (pinfunction "GND_10") (pintype "power_in"))
      (node (ref "U3") (pin "3") (pinfunction "GNDANA_3") (pintype "bidirectional"))
      (node (ref "U3") (pin "35") (pinfunction "GND_35") (pintype "bidirectional"))
      (node (ref "U3") (pin "46") (pinfunction "GNDBU_46") (pintype "bidirectional"))
      (node (ref "U3") (pin "48") (pinfunction "JTAGSEL_48") (pintype "bidirectional"))
      (node (ref "U3") (pin "61") (pinfunction "GND_61") (pintype "bidirectional"))
      (node (ref "U3") (pin "72") (pinfunction "GNDPLL_72") (pintype "bidirectional"))
      (node (ref "U3") (pin "89") (pinfunction "GND_89") (pintype "bidirectional"))
      (node (ref "U4") (pin "5") (pinfunction "GND_5") (pintype "bidirectional"))
    )
    (net (code "67") (name "Net-(D1-PadA)") (class "Default")
      (node (ref "D1") (pin "A") (pinfunction "A_A") (pintype "passive"))
      (node (ref "R2") (pin "2") (pinfunction "2_2") (pintype "passive"))
    )
    (net (code "68") (name "Net-(D2-PadA)") (class "Default")
      (node (ref "D2") (pin "A") (pinfunction "A_A") (pintype "passive"))
      (node (ref "R3") (pin "2") (pinfunction "2_2") (pintype "passive"))
    )
    (net (code "69") (name "Net-(D3-PadA)") (class "Default")
      (node (ref "D3") (pin "A") (pinfunction "A_A") (pintype "passive"))
      (node (ref "R4") (pin "2") (pinfunction "2_2") (pintype "passive"))
    )
    (net (code "70") (name "Net-(R11-Pad2)") (class "Default")
      (node (ref "R11") (pin "2") (pinfunction "2_2") (pintype "passive"))
      (node (ref "SJ2") (pin "1") (pinfunction "1_1") (pintype "passive"))
    )
    (net (code "71") (name "Net-(R21A-2)") (class "Default")
      (node (ref "JP2") (pin "1") (pinfunction "1_1") (pintype "bidirectional"))
      (node (ref "R21") (pin "8") (pinfunction "2_8") (pintype "passive"))
    )
    (net (code "72") (name "Net-(R21B-2)") (class "Default")
      (node (ref "JP2") (pin "2") (pinfunction "2_2") (pintype "bidirectional"))
      (node (ref "R21") (pin "7") (pinfunction "2_7") (pintype "passive"))
    )
    (net (code "73") (name "Net-(R21C-2)") (class "Default")
      (node (ref "JP2") (pin "4") (pinfunction "4_4") (pintype "bidirectional"))
      (node (ref "R21") (pin "5") (pinfunction "2_5") (pintype "passive"))
    )
    (net (code "74") (name "Net-(R21D-2)") (class "Default")
      (node (ref "JP2") (pin "3") (pinfunction "3_3") (pintype "bidirectional"))
      (node (ref "R21") (pin "6") (pinfunction "2_6") (pintype "passive"))
    )
    (net (code "75") (name "Net-(R22A-2)") (class "Default")
      (node (ref "JP2") (pin "5") (pinfunction "5_5") (pintype "bidirectional"))
      (node (ref "R22") (pin "8") (pinfunction "2_8") (pintype "passive"))
    )
    (net (code "76") (name "Net-(R22B-2)") (class "Default")
      (node (ref "JP2") (pin "6") (pinfunction "6_6") (pintype "bidirectional"))
      (node (ref "R22") (pin "7") (pinfunction "2_7") (pintype "passive"))
    )
    (net (code "77") (name "Net-(R22C-2)") (class "Default")
      (node (ref "JP2") (pin "8") (pinfunction "8_8") (pintype "bidirectional"))
      (node (ref "R22") (pin "5") (pinfunction "2_5") (pintype "passive"))
    )
    (net (code "78") (name "Net-(R22D-2)") (class "Default")
      (node (ref "JP2") (pin "7") (pinfunction "7_7") (pintype "bidirectional"))
      (node (ref "R22") (pin "6") (pinfunction "2_6") (pintype "passive"))
    )
    (net (code "79") (name "Net-(U1-SW)") (class "Default")
      (node (ref "L2") (pin "1") (pinfunction "1_1") (pintype "passive"))
      (node (ref "U1") (pin "5") (pinfunction "SW_5") (pintype "bidirectional"))
    )
    (net (code "80") (name "Net-(U3-AD12BVREF)") (class "Default")
      (node (ref "C17") (pin "2") (pinfunction "2_2") (pintype "passive"))
      (node (ref "C18") (pin "2") (pinfunction "2_2") (pintype "passive"))
      (node (ref "L4") (pin "2") (pinfunction "2_2") (pintype "passive"))
      (node (ref "U3") (pin "2") (pinfunction "ADVREF_2") (pintype "bidirectional"))
      (node (ref "U3") (pin "4") (pinfunction "AD12BVREF_4") (pintype "bidirectional"))
    )
    (net (code "81") (name "Net-(U3-DFSDM)") (class "Default")
      (node (ref "R6") (pin "2") (pinfunction "2_2") (pintype "passive"))
      (node (ref "U3") (pin "80") (pinfunction "DFSDM_80") (pintype "bidirectional"))
    )
    (net (code "82") (name "Net-(U3-DFSDP)") (class "Default")
      (node (ref "R8") (pin "2") (pinfunction "2_2") (pintype "passive"))
      (node (ref "U3") (pin "81") (pinfunction "DFSDP_81") (pintype "bidirectional"))
    )
    (net (code "83") (name "Net-(U3-FWUP)") (class "Default")
      (node (ref "R7") (pin "2") (pinfunction "2_2") (pintype "passive"))
      (node (ref "U3") (pin "42") (pinfunction "FWUP_42") (pintype "bidirectional"))
    )
    (net (code "84") (name "Net-(U3-VBG)") (class "Default")
      (node (ref "C4") (pin "2") (pinfunction "2_2") (pintype "passive"))
      (node (ref "R5") (pin "2") (pinfunction "2_2") (pintype "passive"))
      (node (ref "U3") (pin "78") (pinfunction "VBG_78") (pintype "bidirectional"))
    )
    (net (code "85") (name "Net-(U3-XIN)") (class "Default")
      (node (ref "C7") (pin "2") (pinfunction "2_2") (pintype "passive"))
      (node (ref "U3") (pin "75") (pinfunction "XIN_75") (pintype "bidirectional"))
      (node (ref "Y1") (pin "3") (pinfunction "2_3") (pintype "passive"))
    )
    (net (code "86") (name "Net-(U3-XOUT)") (class "Default")
      (node (ref "C6") (pin "2") (pinfunction "2_2") (pintype "passive"))
      (node (ref "U3") (pin "74") (pinfunction "XOUT_74") (pintype "bidirectional"))
      (node (ref "Y1") (pin "1") (pinfunction "1_1") (pintype "passive"))
    )
    (net (code "87") (name "unconnected-(JTAG-Pad7)") (class "Default")
      (node (ref "JTAG") (pin "7") (pinfunction "7_7") (pintype "passive"))
    )
    (net (code "88") (name "unconnected-(SJ2-Pad3)") (class "Default")
      (node (ref "SJ2") (pin "3") (pinfunction "3_3") (pintype "passive"))
    )
    (net (code "89") (name "unconnected-(U3-ERASE-Pad43)") (class "Default")
      (node (ref "U3") (pin "43") (pinfunction "ERASE_43") (pintype "bidirectional"))
    )
    (net (code "90") (name "unconnected-(U3-NRSTB{slash}~{ASYNC_RESET}-Pad47)") (class "Default")
      (node (ref "U3") (pin "47") (pinfunction "NRSTB/~{ASYNC_RESET}_47") (pintype "bidirectional"))
    )
    (net (code "91") (name "unconnected-(U3-PA6{slash}MCDA1{slash}PWMH2-Pad32)") (class "Default")
      (node (ref "U3") (pin "32") (pinfunction "PA6/MCDA1/PWMH2_32") (pintype "bidirectional"))
    )
    (net (code "92") (name "unconnected-(U3-PA7{slash}MCDA2{slash}PWML0-Pad33)") (class "Default")
      (node (ref "U3") (pin "33") (pinfunction "PA7/MCDA2/PWML0_33") (pintype "bidirectional"))
    )
    (net (code "93") (name "unconnected-(U3-PA13{slash}MISO-Pad10)") (class "Default")
      (node (ref "U3") (pin "10") (pinfunction "PA13/MISO_10") (pintype "bidirectional"))
    )
    (net (code "94") (name "unconnected-(U3-PA14{slash}MOSI-Pad11)") (class "Default")
      (node (ref "U3") (pin "11") (pinfunction "PA14/MOSI_11") (pintype "bidirectional"))
    )
    (net (code "95") (name "unconnected-(U3-PA15{slash}SPCK{slash}PWMH2-Pad12)") (class "Default")
      (node (ref "U3") (pin "12") (pinfunction "PA15/SPCK/PWMH2_12") (pintype "bidirectional"))
    )
    (net (code "96") (name "unconnected-(U3-PA17{slash}SCK0{slash}AD12BTRG-Pad14)") (class "Default")
      (node (ref "U3") (pin "14") (pinfunction "PA17/SCK0/AD12BTRG_14") (pintype "bidirectional"))
    )
    (net (code "97") (name "unconnected-(U3-PA26{slash}TD{slash}TCLK2-Pad25)") (class "Default")
      (node (ref "U3") (pin "25") (pinfunction "PA26/TD/TCLK2_25") (pintype "bidirectional"))
    )
    (net (code "98") (name "unconnected-(U3-PA27{slash}RD{slash}PCK0-Pad96)") (class "Default")
      (node (ref "U3") (pin "96") (pinfunction "PA27/RD/PCK0_96") (pintype "bidirectional"))
    )
    (net (code "99") (name "unconnected-(U3-PA29{slash}RK{slash}PWMH1-Pad85)") (class "Default")
      (node (ref "U3") (pin "85") (pinfunction "PA29/RK/PWMH1_85") (pintype "bidirectional"))
    )
    (net (code "100") (name "unconnected-(U3-PA31{slash}RF{slash}TIOB2-Pad86)") (class "Default")
      (node (ref "U3") (pin "86") (pinfunction "PA31/RF/TIOB2_86") (pintype "bidirectional"))
    )
    (net (code "101") (name "unconnected-(U3-PB0{slash}PWMH0{slash}A2-Pad90)") (class "Default")
      (node (ref "U3") (pin "90") (pinfunction "PB0/PWMH0/A2_90") (pintype "bidirectional"))
    )
    (net (code "102") (name "unconnected-(U3-PB1{slash}PWMH1{slash}A3-Pad91)") (class "Default")
      (node (ref "U3") (pin "91") (pinfunction "PB1/PWMH1/A3_91") (pintype "bidirectional"))
    )
    (net (code "103") (name "unconnected-(U3-PB2{slash}PWMH2{slash}A4-Pad92)") (class "Default")
      (node (ref "U3") (pin "92") (pinfunction "PB2/PWMH2/A4_92") (pintype "bidirectional"))
    )
    (net (code "104") (name "unconnected-(U3-PB9{slash}D0{slash}DTR0-Pad71)") (class "Default")
      (node (ref "U3") (pin "71") (pinfunction "PB9/D0/DTR0_71") (pintype "bidirectional"))
    )
    (net (code "105") (name "unconnected-(U3-PB10{slash}D1{slash}DSR0-Pad70)") (class "Default")
      (node (ref "U3") (pin "70") (pinfunction "PB10/D1/DSR0_70") (pintype "bidirectional"))
    )
    (net (code "106") (name "unconnected-(U3-PB11{slash}D2{slash}DCD0-Pad93)") (class "Default")
      (node (ref "U3") (pin "93") (pinfunction "PB11/D2/DCD0_93") (pintype "bidirectional"))
    )
    (net (code "107") (name "unconnected-(U3-PB12{slash}D3{slash}RI0-Pad94)") (class "Default")
      (node (ref "U3") (pin "94") (pinfunction "PB12/D3/RI0_94") (pintype "bidirectional"))
    )
    (net (code "108") (name "unconnected-(U3-PB13{slash}D4{slash}PWMH0-Pad95)") (class "Default")
      (node (ref "U3") (pin "95") (pinfunction "PB13/D4/PWMH0_95") (pintype "bidirectional"))
    )
    (net (code "109") (name "unconnected-(U3-PB15{slash}D6{slash}PWMH2-Pad16)") (class "Default")
      (node (ref "U3") (pin "16") (pinfunction "PB15/D6/PWMH2_16") (pintype "bidirectional"))
    )
    (net (code "110") (name "unconnected-(U3-PB16{slash}D7{slash}PWMH3-Pad15)") (class "Default")
      (node (ref "U3") (pin "15") (pinfunction "PB16/D7/PWMH3_15") (pintype "bidirectional"))
    )
    (net (code "111") (name "unconnected-(U3-PB21{slash}A21{slash}RTS2-Pad64)") (class "Default")
      (node (ref "U3") (pin "64") (pinfunction "PB21/A21/RTS2_64") (pintype "bidirectional"))
    )
    (net (code "112") (name "unconnected-(U3-PB22{slash}A22{slash}CTS2-Pad63)") (class "Default")
      (node (ref "U3") (pin "63") (pinfunction "PB22/A22/CTS2_63") (pintype "bidirectional"))
    )
    (net (code "113") (name "unconnected-(U3-TST-Pad44)") (class "Default")
      (node (ref "U3") (pin "44") (pinfunction "TST_44") (pintype "bidirectional"))
    )
    (net (code "114") (name "unconnected-(U3-XIN32-Pad50)") (class "Default")
      (node (ref "U3") (pin "50") (pinfunction "XIN32_50") (pintype "bidirectional"))
    )
    (net (code "115") (name "unconnected-(U3-XOUT32-Pad49)") (class "Default")
      (node (ref "U3") (pin "49") (pinfunction "XOUT32_49") (pintype "bidirectional"))
    )
  )
)
